# untitled.net
KiCad netlist of a schematic drawn in EAGLE
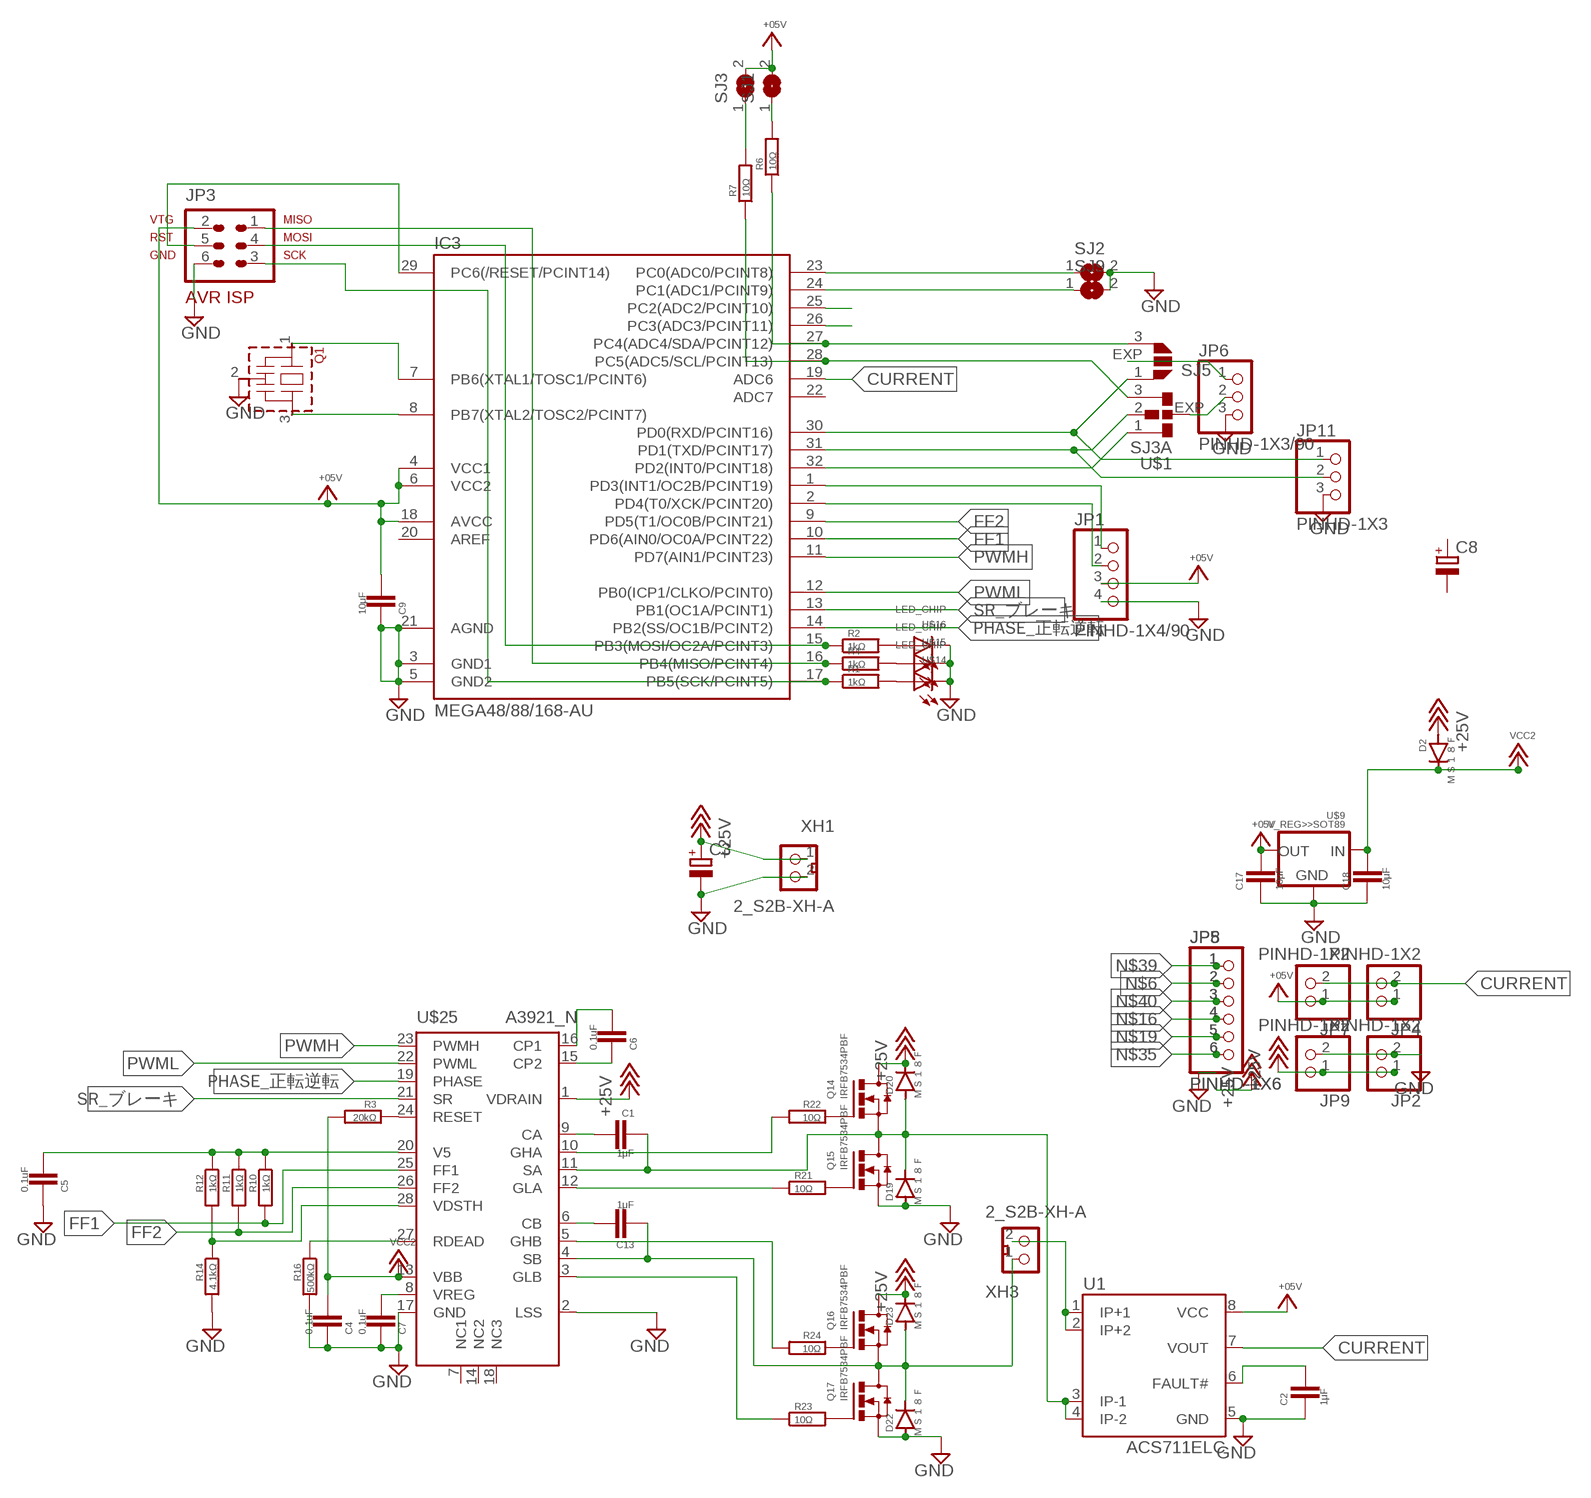
[diagram p0: schematic, sheet 1]

(export (version "E")
  (design (tool "Eeschema 10.0.6"))
  (components
    (comp (ref "C1")
      (value "1μF")
      (footprint "eagle-import:2012")
      (libsource (lib "eagle-import") (part "CAPACITOR{gt}{gt}2012"))
    )
    (comp (ref "C2")
      (value "1μF")
      (footprint "eagle-import:2012")
      (libsource (lib "eagle-import") (part "CAPACITOR{gt}{gt}2012"))
    )
    (comp (ref "C3")
      (value "CPOL-EUUD-6,3X8,8")
      (footprint "eagle-import:UD-6,3X5,8_NICHICON")
      (libsource (lib "eagle-import") (part "CPOL-EUUD-6,3X8,8"))
    )
    (comp (ref "C4")
      (value "0.1uF")
      (footprint "eagle-import:2012")
      (libsource (lib "eagle-import") (part "CAPACITOR{gt}{gt}2012"))
    )
    (comp (ref "C5")
      (value "0.1uF")
      (footprint "eagle-import:2012")
      (libsource (lib "eagle-import") (part "CAPACITOR{gt}{gt}2012"))
    )
    (comp (ref "C6")
      (value "0.1uF")
      (footprint "eagle-import:2012")
      (libsource (lib "eagle-import") (part "CAPACITOR{gt}{gt}2012"))
    )
    (comp (ref "C7")
      (value "0.1uF")
      (footprint "eagle-import:2012")
      (libsource (lib "eagle-import") (part "CAPACITOR{gt}{gt}2012"))
    )
    (comp (ref "C8")
      (value "CPOL-EU150CLZ-1010")
      (footprint "eagle-import:150CLZ-1010")
      (libsource (lib "eagle-import") (part "CPOL-EU150CLZ-1010"))
    )
    (comp (ref "C9")
      (value "10μF")
      (footprint "eagle-import:2012")
      (libsource (lib "eagle-import") (part "CAPACITOR{gt}{gt}2012"))
    )
    (comp (ref "C13")
      (value "1μF")
      (footprint "eagle-import:2012")
      (libsource (lib "eagle-import") (part "CAPACITOR{gt}{gt}2012"))
    )
    (comp (ref "C17")
      (value "10μF")
      (footprint "eagle-import:2012")
      (libsource (lib "eagle-import") (part "CAPACITOR{gt}{gt}2012"))
    )
    (comp (ref "C18")
      (value "10μF")
      (footprint "eagle-import:2012")
      (libsource (lib "eagle-import") (part "CAPACITOR{gt}{gt}2012"))
    )
    (comp (ref "D2")
      (value "ＭＳ１８Ｆ")
      (footprint "eagle-import:MS18F")
      (libsource (lib "eagle-import") (part "DIODE{gt}{gt}MS18F"))
    )
    (comp (ref "D19")
      (value "ＭＳ１８Ｆ")
      (footprint "eagle-import:MS18F")
      (libsource (lib "eagle-import") (part "DIODE{gt}{gt}MS18F"))
    )
    (comp (ref "D20")
      (value "ＭＳ１８Ｆ")
      (footprint "eagle-import:MS18F")
      (libsource (lib "eagle-import") (part "DIODE{gt}{gt}MS18F"))
    )
    (comp (ref "D22")
      (value "ＭＳ１８Ｆ")
      (footprint "eagle-import:MS18F")
      (libsource (lib "eagle-import") (part "DIODE{gt}{gt}MS18F"))
    )
    (comp (ref "D23")
      (value "ＭＳ１８Ｆ")
      (footprint "eagle-import:MS18F")
      (libsource (lib "eagle-import") (part "DIODE{gt}{gt}MS18F"))
    )
    (comp (ref "IC3")
      (value "MEGA48/88/168-AU")
      (footprint "eagle-import:TQFP32-08")
      (libsource (lib "eagle-import") (part "MEGA48/88/168-AU"))
    )
    (comp (ref "JP1")
      (value "PINHD-1X4/90")
      (footprint "eagle-import:1X04_90")
      (libsource (lib "eagle-import") (part "PINHD-1X4/90"))
    )
    (comp (ref "JP2")
      (value "PINHD-1X2")
      (footprint "eagle-import:1X02")
      (libsource (lib "eagle-import") (part "PINHD-1X2"))
    )
    (comp (ref "JP3")
      (value "AVR-ISP-6")
      (footprint "eagle-import:AVR-ISP-6")
      (libsource (lib "eagle-import") (part "AVR-ISP-6"))
    )
    (comp (ref "JP4")
      (value "PINHD-1X2")
      (footprint "eagle-import:1X02")
      (libsource (lib "eagle-import") (part "PINHD-1X2"))
    )
    (comp (ref "JP5")
      (value "PINHD-1X6")
      (footprint "eagle-import:1X06")
      (libsource (lib "eagle-import") (part "PINHD-1X6"))
    )
    (comp (ref "JP6")
      (value "PINHD-1X3/90")
      (footprint "eagle-import:1X03_90")
      (libsource (lib "eagle-import") (part "PINHD-1X3/90"))
    )
    (comp (ref "JP7")
      (value "PINHD-1X2")
      (footprint "eagle-import:1X02")
      (libsource (lib "eagle-import") (part "PINHD-1X2"))
    )
    (comp (ref "JP8")
      (value "PINHD-1X6")
      (footprint "eagle-import:1X06")
      (libsource (lib "eagle-import") (part "PINHD-1X6"))
    )
    (comp (ref "JP9")
      (value "PINHD-1X2")
      (footprint "eagle-import:1X02")
      (libsource (lib "eagle-import") (part "PINHD-1X2"))
    )
    (comp (ref "JP11")
      (value "PINHD-1X3")
      (footprint "eagle-import:1X03")
      (libsource (lib "eagle-import") (part "PINHD-1X3"))
    )
    (comp (ref "Q1")
      (value "CSTLS_G")
      (footprint "eagle-import:CSTLS_G9")
      (libsource (lib "eagle-import") (part "!murata-resonators(ｾﾗﾛｯｸ)_CSTLS_G"))
    )
    (comp (ref "Q14")
      (value "IRFB7534PBF")
      (footprint "eagle-import:TO252")
      (libsource (lib "eagle-import") (part "MOSFET_N{gt}{gt}TO252"))
    )
    (comp (ref "Q15")
      (value "IRFB7534PBF")
      (footprint "eagle-import:TO252")
      (libsource (lib "eagle-import") (part "MOSFET_N{gt}{gt}TO252"))
    )
    (comp (ref "Q16")
      (value "IRFB7534PBF")
      (footprint "eagle-import:TO252")
      (libsource (lib "eagle-import") (part "MOSFET_N{gt}{gt}TO252"))
    )
    (comp (ref "Q17")
      (value "IRFB7534PBF")
      (footprint "eagle-import:TO252")
      (libsource (lib "eagle-import") (part "MOSFET_N{gt}{gt}TO252"))
    )
    (comp (ref "R1")
      (value "1kΩ")
      (footprint "eagle-import:2012")
      (libsource (lib "eagle-import") (part "REGISTER{gt}{gt}2012"))
    )
    (comp (ref "R2")
      (value "1kΩ")
      (footprint "eagle-import:2012")
      (libsource (lib "eagle-import") (part "REGISTER{gt}{gt}2012"))
    )
    (comp (ref "R3")
      (value "20kΩ")
      (footprint "eagle-import:2012")
      (libsource (lib "eagle-import") (part "REGISTER{gt}{gt}2012"))
    )
    (comp (ref "R4")
      (value "1kΩ")
      (footprint "eagle-import:2012")
      (libsource (lib "eagle-import") (part "REGISTER{gt}{gt}2012"))
    )
    (comp (ref "R6")
      (value "10Ω")
      (footprint "eagle-import:2012")
      (libsource (lib "eagle-import") (part "REGISTER{gt}{gt}2012"))
    )
    (comp (ref "R7")
      (value "10Ω")
      (footprint "eagle-import:2012")
      (libsource (lib "eagle-import") (part "REGISTER{gt}{gt}2012"))
    )
    (comp (ref "R10")
      (value "1kΩ")
      (footprint "eagle-import:2012")
      (libsource (lib "eagle-import") (part "REGISTER{gt}{gt}2012"))
    )
    (comp (ref "R11")
      (value "1kΩ")
      (footprint "eagle-import:2012")
      (libsource (lib "eagle-import") (part "REGISTER{gt}{gt}2012"))
    )
    (comp (ref "R12")
      (value "1kΩ")
      (footprint "eagle-import:2012")
      (libsource (lib "eagle-import") (part "REGISTER{gt}{gt}2012"))
    )
    (comp (ref "R14")
      (value "4.1kΩ")
      (footprint "eagle-import:2012")
      (libsource (lib "eagle-import") (part "REGISTER{gt}{gt}2012"))
    )
    (comp (ref "R16")
      (value "500kΩ")
      (footprint "eagle-import:2012")
      (libsource (lib "eagle-import") (part "REGISTER{gt}{gt}2012"))
    )
    (comp (ref "R21")
      (value "10Ω")
      (footprint "eagle-import:2012")
      (libsource (lib "eagle-import") (part "REGISTER{gt}{gt}2012"))
    )
    (comp (ref "R22")
      (value "10Ω")
      (footprint "eagle-import:2012")
      (libsource (lib "eagle-import") (part "REGISTER{gt}{gt}2012"))
    )
    (comp (ref "R23")
      (value "10Ω")
      (footprint "eagle-import:2012")
      (libsource (lib "eagle-import") (part "REGISTER{gt}{gt}2012"))
    )
    (comp (ref "R24")
      (value "10Ω")
      (footprint "eagle-import:2012")
      (libsource (lib "eagle-import") (part "REGISTER{gt}{gt}2012"))
    )
    (comp (ref "SJ1")
      (value "SJSS")
      (footprint "eagle-import:SJ_B")
      (libsource (lib "eagle-import") (part "SJSS"))
    )
    (comp (ref "SJ2")
      (value "SJSS")
      (footprint "eagle-import:SJ_B")
      (libsource (lib "eagle-import") (part "SJSS"))
    )
    (comp (ref "SJ3")
      (value "SJSS")
      (footprint "eagle-import:SJ_B")
      (libsource (lib "eagle-import") (part "SJSS"))
    )
    (comp (ref "SJ5")
      (value "SJ2")
      (footprint "eagle-import:SJ2_A")
      (libsource (lib "eagle-import") (part "SJ2"))
    )
    (comp (ref "SJ9")
      (value "SJSS")
      (footprint "eagle-import:SJ_B")
      (libsource (lib "eagle-import") (part "SJSS"))
    )
    (comp (ref "U$1")
      (value "SJ3A")
      (footprint "eagle-import:SJ3_A")
      (libsource (lib "eagle-import") (part "SJ3A"))
    )
    (comp (ref "U$9")
      (value "V_REG>>SOT89")
      (footprint "eagle-import:SOT89")
      (libsource (lib "eagle-import") (part "V_REG{gt}{gt}SOT89"))
    )
    (comp (ref "U$14")
      (value "LED_CHIP")
      (footprint "eagle-import:2012")
      (libsource (lib "eagle-import") (part "LED_CHIP"))
    )
    (comp (ref "U$15")
      (value "LED_CHIP")
      (footprint "eagle-import:2012")
      (libsource (lib "eagle-import") (part "LED_CHIP"))
    )
    (comp (ref "U$16")
      (value "LED_CHIP")
      (footprint "eagle-import:2012")
      (libsource (lib "eagle-import") (part "LED_CHIP"))
    )
    (comp (ref "U$25")
      (value "A3921_N")
      (footprint "eagle-import:TSSOP28_N")
      (libsource (lib "eagle-import") (part "A3921_N"))
    )
    (comp (ref "U1")
      (value "ACS711ELC")
      (footprint "eagle-import:SOIC8")
      (libsource (lib "eagle-import") (part "ACS711ELC"))
    )
    (comp (ref "XH1")
      (value "2_S2B-XH-A")
      (footprint "eagle-import:S2B-XH-A")
      (libsource (lib "eagle-import") (part "2_S2B-XH-A"))
    )
    (comp (ref "XH3")
      (value "2_S2B-XH-A")
      (footprint "eagle-import:S2B-XH-A")
      (libsource (lib "eagle-import") (part "2_S2B-XH-A"))
    )
  )
  (nets
    (net (code "1") (name "+05V") (class "Default")
      (node (ref "C17") (pin "1") (pinfunction "1_1") (pintype "passive"))
      (node (ref "C9") (pin "1") (pinfunction "1_1") (pintype "passive"))
      (node (ref "IC3") (pin "18") (pinfunction "AVCC_18") (pintype "passive"))
      (node (ref "IC3") (pin "4") (pinfunction "VCC1_4") (pintype "power_in"))
      (node (ref "IC3") (pin "6") (pinfunction "VCC2_6") (pintype "power_in"))
      (node (ref "JP1") (pin "3") (pinfunction "3_3") (pintype "passive"))
      (node (ref "JP3") (pin "2") (pinfunction "2_2") (pintype "passive"))
      (node (ref "JP4") (pin "1") (pinfunction "1_1") (pintype "passive"))
      (node (ref "JP7") (pin "1") (pinfunction "1_1") (pintype "passive"))
      (node (ref "SJ1") (pin "2") (pinfunction "2_2") (pintype "passive"))
      (node (ref "SJ3") (pin "2") (pinfunction "2_2") (pintype "passive"))
      (node (ref "U$9") (pin "1") (pinfunction "OUT_1") (pintype "passive"))
      (node (ref "U1") (pin "8") (pinfunction "VCC_8") (pintype "bidirectional"))
    )
    (net (code "2") (name "+25V") (class "Default")
      (node (ref "C3") (pin "+") (pinfunction "+_+") (pintype "passive"))
      (node (ref "D2") (pin "P$1") (pinfunction "A_P$1") (pintype "passive"))
      (node (ref "D20") (pin "P$2") (pinfunction "C_P$2") (pintype "passive"))
      (node (ref "D23") (pin "P$2") (pinfunction "C_P$2") (pintype "passive"))
      (node (ref "JP2") (pin "1") (pinfunction "1_1") (pintype "passive"))
      (node (ref "JP9") (pin "1") (pinfunction "1_1") (pintype "passive"))
      (node (ref "Q14") (pin "3") (pinfunction "D_3") (pintype "passive"))
      (node (ref "Q16") (pin "3") (pinfunction "D_3") (pintype "passive"))
      (node (ref "U$25") (pin "1") (pinfunction "VDRAIN_1") (pintype "power_in"))
      (node (ref "XH1") (pin "1") (pinfunction "1_1") (pintype "passive"))
    )
    (net (code "3") (name "CURRENT") (class "Default")
      (node (ref "IC3") (pin "19") (pinfunction "ADC6_19") (pintype "passive"))
      (node (ref "JP4") (pin "2") (pinfunction "2_2") (pintype "passive"))
      (node (ref "JP7") (pin "2") (pinfunction "2_2") (pintype "passive"))
      (node (ref "U1") (pin "7") (pinfunction "VOUT_7") (pintype "bidirectional"))
    )
    (net (code "4") (name "FF1") (class "Default")
      (node (ref "IC3") (pin "10") (pinfunction "PD6(AIN0/OC0A/PCINT22)_10") (pintype "bidirectional"))
      (node (ref "R10") (pin "2") (pinfunction "2_2") (pintype "passive"))
      (node (ref "U$25") (pin "25") (pinfunction "FF1_25") (pintype "output"))
    )
    (net (code "5") (name "FF2") (class "Default")
      (node (ref "IC3") (pin "9") (pinfunction "PD5(T1/OC0B/PCINT21)_9") (pintype "bidirectional"))
      (node (ref "R11") (pin "2") (pinfunction "2_2") (pintype "passive"))
      (node (ref "U$25") (pin "26") (pinfunction "FF2_26") (pintype "output"))
    )
    (net (code "6") (name "GND") (class "Default")
      (node (ref "C17") (pin "2") (pinfunction "2_2") (pintype "passive"))
      (node (ref "C18") (pin "2") (pinfunction "2_2") (pintype "passive"))
      (node (ref "C2") (pin "2") (pinfunction "2_2") (pintype "passive"))
      (node (ref "C3") (pin "-") (pinfunction "-_-") (pintype "passive"))
      (node (ref "C4") (pin "2") (pinfunction "2_2") (pintype "passive"))
      (node (ref "C5") (pin "2") (pinfunction "2_2") (pintype "passive"))
      (node (ref "C7") (pin "2") (pinfunction "2_2") (pintype "passive"))
      (node (ref "C9") (pin "2") (pinfunction "2_2") (pintype "passive"))
      (node (ref "D19") (pin "P$1") (pinfunction "A_P$1") (pintype "passive"))
      (node (ref "D22") (pin "P$1") (pinfunction "A_P$1") (pintype "passive"))
      (node (ref "IC3") (pin "21") (pinfunction "AGND_21") (pintype "power_in"))
      (node (ref "IC3") (pin "3") (pinfunction "GND1_3") (pintype "power_in"))
      (node (ref "IC3") (pin "5") (pinfunction "GND2_5") (pintype "power_in"))
      (node (ref "JP1") (pin "4") (pinfunction "4_4") (pintype "passive"))
      (node (ref "JP11") (pin "3") (pinfunction "3_3") (pintype "passive"))
      (node (ref "JP2") (pin "2") (pinfunction "2_2") (pintype "passive"))
      (node (ref "JP3") (pin "6") (pinfunction "6_6") (pintype "passive"))
      (node (ref "JP6") (pin "3") (pinfunction "3_3") (pintype "passive"))
      (node (ref "JP9") (pin "2") (pinfunction "2_2") (pintype "passive"))
      (node (ref "Q1") (pin "2") (pinfunction "VSS_2") (pintype "power_in"))
      (node (ref "Q15") (pin "2") (pinfunction "S_2") (pintype "passive"))
      (node (ref "Q17") (pin "2") (pinfunction "S_2") (pintype "passive"))
      (node (ref "R14") (pin "2") (pinfunction "2_2") (pintype "passive"))
      (node (ref "R16") (pin "2") (pinfunction "2_2") (pintype "passive"))
      (node (ref "SJ2") (pin "2") (pinfunction "2_2") (pintype "passive"))
      (node (ref "SJ9") (pin "2") (pinfunction "2_2") (pintype "passive"))
      (node (ref "U$14") (pin "P$2") (pinfunction "C_P$2") (pintype "passive"))
      (node (ref "U$15") (pin "P$2") (pinfunction "C_P$2") (pintype "passive"))
      (node (ref "U$16") (pin "P$2") (pinfunction "C_P$2") (pintype "passive"))
      (node (ref "U$25") (pin "17") (pinfunction "GND_17") (pintype "power_in"))
      (node (ref "U$25") (pin "2") (pinfunction "LSS_2") (pintype "passive"))
      (node (ref "U$9") (pin "2") (pinfunction "GND_2") (pintype "input"))
      (node (ref "U$9") (pin "2.1") (pinfunction "GND_2.1") (pintype "input"))
      (node (ref "U1") (pin "5") (pinfunction "GND_5") (pintype "bidirectional"))
      (node (ref "XH1") (pin "2") (pinfunction "2_2") (pintype "passive"))
    )
    (net (code "7") (name "N$6") (class "Default")
      (node (ref "C13") (pin "2") (pinfunction "2_2") (pintype "passive"))
      (node (ref "D22") (pin "P$2") (pinfunction "C_P$2") (pintype "passive"))
      (node (ref "D23") (pin "P$1") (pinfunction "A_P$1") (pintype "passive"))
      (node (ref "JP5") (pin "2") (pinfunction "2_2") (pintype "passive"))
      (node (ref "JP8") (pin "2") (pinfunction "2_2") (pintype "passive"))
      (node (ref "Q16") (pin "2") (pinfunction "S_2") (pintype "passive"))
      (node (ref "Q17") (pin "3") (pinfunction "D_3") (pintype "passive"))
      (node (ref "U$25") (pin "4") (pinfunction "SB_4") (pintype "output"))
      (node (ref "XH3") (pin "1") (pinfunction "1_1") (pintype "passive"))
    )
    (net (code "8") (name "N$16") (class "Default")
      (node (ref "JP5") (pin "4") (pinfunction "4_4") (pintype "passive"))
      (node (ref "JP8") (pin "4") (pinfunction "4_4") (pintype "passive"))
      (node (ref "R22") (pin "2") (pinfunction "2_2") (pintype "passive"))
      (node (ref "U$25") (pin "10") (pinfunction "GHA_10") (pintype "output"))
    )
    (net (code "9") (name "N$19") (class "Default")
      (node (ref "C1") (pin "2") (pinfunction "2_2") (pintype "passive"))
      (node (ref "D19") (pin "P$2") (pinfunction "C_P$2") (pintype "passive"))
      (node (ref "D20") (pin "P$1") (pinfunction "A_P$1") (pintype "passive"))
      (node (ref "JP5") (pin "5") (pinfunction "5_5") (pintype "passive"))
      (node (ref "JP8") (pin "5") (pinfunction "5_5") (pintype "passive"))
      (node (ref "Q14") (pin "2") (pinfunction "S_2") (pintype "passive"))
      (node (ref "Q15") (pin "3") (pinfunction "D_3") (pintype "passive"))
      (node (ref "U$25") (pin "11") (pinfunction "SA_11") (pintype "output"))
      (node (ref "U1") (pin "3") (pinfunction "IP-1_3") (pintype "bidirectional"))
      (node (ref "U1") (pin "4") (pinfunction "IP-2_4") (pintype "bidirectional"))
    )
    (net (code "10") (name "N$35") (class "Default")
      (node (ref "JP5") (pin "6") (pinfunction "6_6") (pintype "passive"))
      (node (ref "JP8") (pin "6") (pinfunction "6_6") (pintype "passive"))
      (node (ref "R21") (pin "1") (pinfunction "1_1") (pintype "passive"))
      (node (ref "U$25") (pin "12") (pinfunction "GLA_12") (pintype "output"))
    )
    (net (code "11") (name "N$39") (class "Default")
      (node (ref "JP5") (pin "1") (pinfunction "1_1") (pintype "passive"))
      (node (ref "JP8") (pin "1") (pinfunction "1_1") (pintype "passive"))
      (node (ref "R24") (pin "2") (pinfunction "2_2") (pintype "passive"))
      (node (ref "U$25") (pin "5") (pinfunction "GHB_5") (pintype "output"))
    )
    (net (code "12") (name "N$40") (class "Default")
      (node (ref "JP5") (pin "3") (pinfunction "3_3") (pintype "passive"))
      (node (ref "JP8") (pin "3") (pinfunction "3_3") (pintype "passive"))
      (node (ref "R23") (pin "1") (pinfunction "1_1") (pintype "passive"))
      (node (ref "U$25") (pin "3") (pinfunction "GLB_3") (pintype "output"))
    )
    (net (code "13") (name "Net-(IC3-PB3(MOSI{slash}OC2A{slash}PCINT3))") (class "Default")
      (node (ref "IC3") (pin "15") (pinfunction "PB3(MOSI/OC2A/PCINT3)_15") (pintype "bidirectional"))
      (node (ref "JP3") (pin "4") (pinfunction "4_4") (pintype "passive"))
      (node (ref "R2") (pin "1") (pinfunction "1_1") (pintype "passive"))
    )
    (net (code "14") (name "Net-(IC3-PB4(MISO{slash}PCINT4))") (class "Default")
      (node (ref "IC3") (pin "16") (pinfunction "PB4(MISO/PCINT4)_16") (pintype "bidirectional"))
      (node (ref "JP3") (pin "1") (pinfunction "1_1") (pintype "passive"))
      (node (ref "R4") (pin "1") (pinfunction "1_1") (pintype "passive"))
    )
    (net (code "15") (name "Net-(IC3-PB5(SCK{slash}PCINT5))") (class "Default")
      (node (ref "IC3") (pin "17") (pinfunction "PB5(SCK/PCINT5)_17") (pintype "bidirectional"))
      (node (ref "JP3") (pin "3") (pinfunction "3_3") (pintype "passive"))
      (node (ref "R1") (pin "1") (pinfunction "1_1") (pintype "passive"))
    )
    (net (code "16") (name "Net-(IC3-PB6(XTAL1{slash}TOSC1{slash}PCINT6))") (class "Default")
      (node (ref "IC3") (pin "7") (pinfunction "PB6(XTAL1/TOSC1/PCINT6)_7") (pintype "bidirectional"))
      (node (ref "Q1") (pin "1") (pinfunction "1_1") (pintype "output"))
    )
    (net (code "17") (name "Net-(IC3-PB7(XTAL2{slash}TOSC2{slash}PCINT7))") (class "Default")
      (node (ref "IC3") (pin "8") (pinfunction "PB7(XTAL2/TOSC2/PCINT7)_8") (pintype "bidirectional"))
      (node (ref "Q1") (pin "3") (pinfunction "3_3") (pintype "input"))
    )
    (net (code "18") (name "Net-(IC3-PC0(ADC0{slash}PCINT8))") (class "Default")
      (node (ref "IC3") (pin "23") (pinfunction "PC0(ADC0/PCINT8)_23") (pintype "bidirectional"))
      (node (ref "SJ2") (pin "1") (pinfunction "1_1") (pintype "passive"))
    )
    (net (code "19") (name "Net-(IC3-PC1(ADC1{slash}PCINT9))") (class "Default")
      (node (ref "IC3") (pin "24") (pinfunction "PC1(ADC1/PCINT9)_24") (pintype "bidirectional"))
      (node (ref "SJ9") (pin "1") (pinfunction "1_1") (pintype "passive"))
    )
    (net (code "20") (name "Net-(IC3-PC4(ADC4{slash}SDA{slash}PCINT12))") (class "Default")
      (node (ref "IC3") (pin "27") (pinfunction "PC4(ADC4/SDA/PCINT12)_27") (pintype "bidirectional"))
      (node (ref "R6") (pin "1") (pinfunction "1_1") (pintype "passive"))
      (node (ref "SJ5") (pin "3") (pinfunction "3_3") (pintype "passive"))
    )
    (net (code "21") (name "Net-(IC3-PC5(ADC5{slash}SCL{slash}PCINT13))") (class "Default")
      (node (ref "IC3") (pin "28") (pinfunction "PC5(ADC5/SCL/PCINT13)_28") (pintype "bidirectional"))
      (node (ref "R7") (pin "1") (pinfunction "1_1") (pintype "passive"))
      (node (ref "U$1") (pin "3") (pinfunction "3_3") (pintype "passive"))
    )
    (net (code "22") (name "Net-(IC3-PC6({slash}RESET{slash}PCINT14))") (class "Default")
      (node (ref "IC3") (pin "29") (pinfunction "PC6(/RESET/PCINT14)_29") (pintype "bidirectional"))
      (node (ref "JP3") (pin "5") (pinfunction "5_5") (pintype "passive"))
    )
    (net (code "23") (name "Net-(IC3-PD0(RXD{slash}PCINT16))") (class "Default")
      (node (ref "IC3") (pin "30") (pinfunction "PD0(RXD/PCINT16)_30") (pintype "bidirectional"))
      (node (ref "JP11") (pin "1") (pinfunction "1_1") (pintype "passive"))
      (node (ref "SJ5") (pin "1") (pinfunction "1_1") (pintype "passive"))
    )
    (net (code "24") (name "Net-(IC3-PD1(TXD{slash}PCINT17))") (class "Default")
      (node (ref "IC3") (pin "31") (pinfunction "PD1(TXD/PCINT17)_31") (pintype "bidirectional"))
      (node (ref "JP11") (pin "2") (pinfunction "2_2") (pintype "passive"))
      (node (ref "U$1") (pin "2") (pinfunction "2_2") (pintype "passive"))
    )
    (net (code "25") (name "Net-(IC3-PD2(INT0{slash}PCINT18))") (class "Default")
      (node (ref "IC3") (pin "32") (pinfunction "PD2(INT0/PCINT18)_32") (pintype "bidirectional"))
      (node (ref "U$1") (pin "1") (pinfunction "1_1") (pintype "passive"))
    )
    (net (code "26") (name "Net-(IC3-PD3(INT1{slash}OC2B{slash}PCINT19))") (class "Default")
      (node (ref "IC3") (pin "1") (pinfunction "PD3(INT1/OC2B/PCINT19)_1") (pintype "bidirectional"))
      (node (ref "JP1") (pin "1") (pinfunction "1_1") (pintype "passive"))
    )
    (net (code "27") (name "Net-(IC3-PD4(T0{slash}XCK{slash}PCINT20))") (class "Default")
      (node (ref "IC3") (pin "2") (pinfunction "PD4(T0/XCK/PCINT20)_2") (pintype "bidirectional"))
      (node (ref "JP1") (pin "2") (pinfunction "2_2") (pintype "passive"))
    )
    (net (code "28") (name "Net-(JP6-Pad2)") (class "Default")
      (node (ref "JP6") (pin "2") (pinfunction "2_2") (pintype "passive"))
      (node (ref "U$1") (pin "EXP") (pinfunction "EXP_EXP") (pintype "passive"))
    )
    (net (code "29") (name "Net-(Q14-G)") (class "Default")
      (node (ref "Q14") (pin "1") (pinfunction "G_1") (pintype "passive"))
      (node (ref "R22") (pin "1") (pinfunction "1_1") (pintype "passive"))
    )
    (net (code "30") (name "Net-(Q15-G)") (class "Default")
      (node (ref "Q15") (pin "1") (pinfunction "G_1") (pintype "passive"))
      (node (ref "R21") (pin "2") (pinfunction "2_2") (pintype "passive"))
    )
    (net (code "31") (name "Net-(Q16-G)") (class "Default")
      (node (ref "Q16") (pin "1") (pinfunction "G_1") (pintype "passive"))
      (node (ref "R24") (pin "1") (pinfunction "1_1") (pintype "passive"))
    )
    (net (code "32") (name "Net-(Q17-G)") (class "Default")
      (node (ref "Q17") (pin "1") (pinfunction "G_1") (pintype "passive"))
      (node (ref "R23") (pin "2") (pinfunction "2_2") (pintype "passive"))
    )
    (net (code "33") (name "Net-(R6-Pad2)") (class "Default")
      (node (ref "R6") (pin "2") (pinfunction "2_2") (pintype "passive"))
      (node (ref "SJ1") (pin "1") (pinfunction "1_1") (pintype "passive"))
    )
    (net (code "34") (name "Net-(R7-Pad2)") (class "Default")
      (node (ref "R7") (pin "2") (pinfunction "2_2") (pintype "passive"))
      (node (ref "SJ3") (pin "1") (pinfunction "1_1") (pintype "passive"))
    )
    (net (code "35") (name "Net-(SJ5-2)") (class "Default")
      (node (ref "JP6") (pin "1") (pinfunction "1_1") (pintype "passive"))
      (node (ref "SJ5") (pin "EXP") (pinfunction "2_EXP") (pintype "passive"))
    )
    (net (code "36") (name "Net-(U$14-A)") (class "Default")
      (node (ref "R1") (pin "2") (pinfunction "2_2") (pintype "passive"))
      (node (ref "U$14") (pin "P$1") (pinfunction "A_P$1") (pintype "passive"))
    )
    (net (code "37") (name "Net-(U$15-A)") (class "Default")
      (node (ref "R4") (pin "2") (pinfunction "2_2") (pintype "passive"))
      (node (ref "U$15") (pin "P$1") (pinfunction "A_P$1") (pintype "passive"))
    )
    (net (code "38") (name "Net-(U$16-A)") (class "Default")
      (node (ref "R2") (pin "2") (pinfunction "2_2") (pintype "passive"))
      (node (ref "U$16") (pin "P$1") (pinfunction "A_P$1") (pintype "passive"))
    )
    (net (code "39") (name "Net-(U$25-CA)") (class "Default")
      (node (ref "C1") (pin "1") (pinfunction "1_1") (pintype "passive"))
      (node (ref "U$25") (pin "9") (pinfunction "CA_9") (pintype "input"))
    )
    (net (code "40") (name "Net-(U$25-CB)") (class "Default")
      (node (ref "C13") (pin "1") (pinfunction "1_1") (pintype "passive"))
      (node (ref "U$25") (pin "6") (pinfunction "CB_6") (pintype "input"))
    )
    (net (code "41") (name "Net-(U$25-CP1)") (class "Default")
      (node (ref "C6") (pin "1") (pinfunction "1_1") (pintype "passive"))
      (node (ref "U$25") (pin "16") (pinfunction "CP1_16") (pintype "passive"))
    )
    (net (code "42") (name "Net-(U$25-CP2)") (class "Default")
      (node (ref "C6") (pin "2") (pinfunction "2_2") (pintype "passive"))
      (node (ref "U$25") (pin "15") (pinfunction "CP2_15") (pintype "passive"))
    )
    (net (code "43") (name "Net-(U$25-RDEAD)") (class "Default")
      (node (ref "R16") (pin "1") (pinfunction "1_1") (pintype "passive"))
      (node (ref "U$25") (pin "27") (pinfunction "RDEAD_27") (pintype "input"))
    )
    (net (code "44") (name "Net-(U$25-RESET)") (class "Default")
      (node (ref "R3") (pin "1") (pinfunction "1_1") (pintype "passive"))
      (node (ref "U$25") (pin "24") (pinfunction "RESET_24") (pintype "input"))
    )
    (net (code "45") (name "Net-(U$25-V5)") (class "Default")
      (node (ref "C5") (pin "1") (pinfunction "1_1") (pintype "passive"))
      (node (ref "R10") (pin "1") (pinfunction "1_1") (pintype "passive"))
      (node (ref "R11") (pin "1") (pinfunction "1_1") (pintype "passive"))
      (node (ref "R12") (pin "1") (pinfunction "1_1") (pintype "passive"))
      (node (ref "U$25") (pin "20") (pinfunction "V5_20") (pintype "power_in"))
    )
    (net (code "46") (name "Net-(U$25-VDSTH)") (class "Default")
      (node (ref "R12") (pin "2") (pinfunction "2_2") (pintype "passive"))
      (node (ref "R14") (pin "1") (pinfunction "1_1") (pintype "passive"))
      (node (ref "U$25") (pin "28") (pinfunction "VDSTH_28") (pintype "input"))
    )
    (net (code "47") (name "Net-(U$25-VREG)") (class "Default")
      (node (ref "C7") (pin "1") (pinfunction "1_1") (pintype "passive"))
      (node (ref "U$25") (pin "8") (pinfunction "VREG_8") (pintype "power_in"))
    )
    (net (code "48") (name "Net-(U1-FAULT#)") (class "Default")
      (node (ref "C2") (pin "1") (pinfunction "1_1") (pintype "passive"))
      (node (ref "U1") (pin "6") (pinfunction "FAULT#_6") (pintype "bidirectional"))
    )
    (net (code "49") (name "Net-(U1-IP+1)") (class "Default")
      (node (ref "U1") (pin "1") (pinfunction "IP+1_1") (pintype "bidirectional"))
      (node (ref "U1") (pin "2") (pinfunction "IP+2_2") (pintype "bidirectional"))
      (node (ref "XH3") (pin "2") (pinfunction "2_2") (pintype "passive"))
    )
    (net (code "50") (name "PHASE_正転逆転") (class "Default")
      (node (ref "IC3") (pin "14") (pinfunction "PB2(SS/OC1B/PCINT2)_14") (pintype "bidirectional"))
      (node (ref "U$25") (pin "19") (pinfunction "PHASE_19") (pintype "input"))
    )
    (net (code "51") (name "PWMH") (class "Default")
      (node (ref "IC3") (pin "11") (pinfunction "PD7(AIN1/PCINT23)_11") (pintype "bidirectional"))
      (node (ref "U$25") (pin "23") (pinfunction "PWMH_23") (pintype "input"))
    )
    (net (code "52") (name "PWML") (class "Default")
      (node (ref "IC3") (pin "12") (pinfunction "PB0(ICP1/CLKO/PCINT0)_12") (pintype "bidirectional"))
      (node (ref "U$25") (pin "22") (pinfunction "PWML_22") (pintype "input"))
    )
    (net (code "53") (name "SR_ブレーキ") (class "Default")
      (node (ref "IC3") (pin "13") (pinfunction "PB1(OC1A/PCINT1)_13") (pintype "bidirectional"))
      (node (ref "U$25") (pin "21") (pinfunction "SR_21") (pintype "input"))
    )
    (net (code "54") (name "VCC2") (class "Default")
      (node (ref "C18") (pin "1") (pinfunction "1_1") (pintype "passive"))
      (node (ref "C4") (pin "1") (pinfunction "1_1") (pintype "passive"))
      (node (ref "D2") (pin "P$2") (pinfunction "C_P$2") (pintype "passive"))
      (node (ref "R3") (pin "2") (pinfunction "2_2") (pintype "passive"))
      (node (ref "U$25") (pin "13") (pinfunction "VBB_13") (pintype "power_in"))
      (node (ref "U$9") (pin "3") (pinfunction "IN_3") (pintype "input"))
    )
    (net (code "55") (name "unconnected-(C8-Pad+)") (class "Default")
      (node (ref "C8") (pin "+") (pinfunction "+_+") (pintype "passive"))
    )
    (net (code "56") (name "unconnected-(C8-Pad-)") (class "Default")
      (node (ref "C8") (pin "-") (pinfunction "-_-") (pintype "passive"))
    )
    (net (code "57") (name "unconnected-(IC3-ADC7-Pad22)") (class "Default")
      (node (ref "IC3") (pin "22") (pinfunction "ADC7_22") (pintype "passive"))
    )
    (net (code "58") (name "unconnected-(IC3-AREF-Pad20)") (class "Default")
      (node (ref "IC3") (pin "20") (pinfunction "AREF_20") (pintype "passive"))
    )
    (net (code "59") (name "unconnected-(IC3-PC2(ADC2{slash}PCINT10)-Pad25)") (class "Default")
      (node (ref "IC3") (pin "25") (pinfunction "PC2(ADC2/PCINT10)_25") (pintype "bidirectional"))
    )
    (net (code "60") (name "unconnected-(IC3-PC3(ADC3{slash}PCINT11)-Pad26)") (class "Default")
      (node (ref "IC3") (pin "26") (pinfunction "PC3(ADC3/PCINT11)_26") (pintype "bidirectional"))
    )
    (net (code "61") (name "unconnected-(U$25-NC1-Pad7)") (class "Default")
      (node (ref "U$25") (pin "7") (pinfunction "NC1_7") (pintype "no_connect"))
    )
    (net (code "62") (name "unconnected-(U$25-NC2-Pad14)") (class "Default")
      (node (ref "U$25") (pin "14") (pinfunction "NC2_14") (pintype "no_connect"))
    )
    (net (code "63") (name "unconnected-(U$25-NC3-Pad18)") (class "Default")
      (node (ref "U$25") (pin "18") (pinfunction "NC3_18") (pintype "no_connect"))
    )
  )
)
